# FPGA_Power.net
KiCad netlist of a schematic drawn in Altium Designer
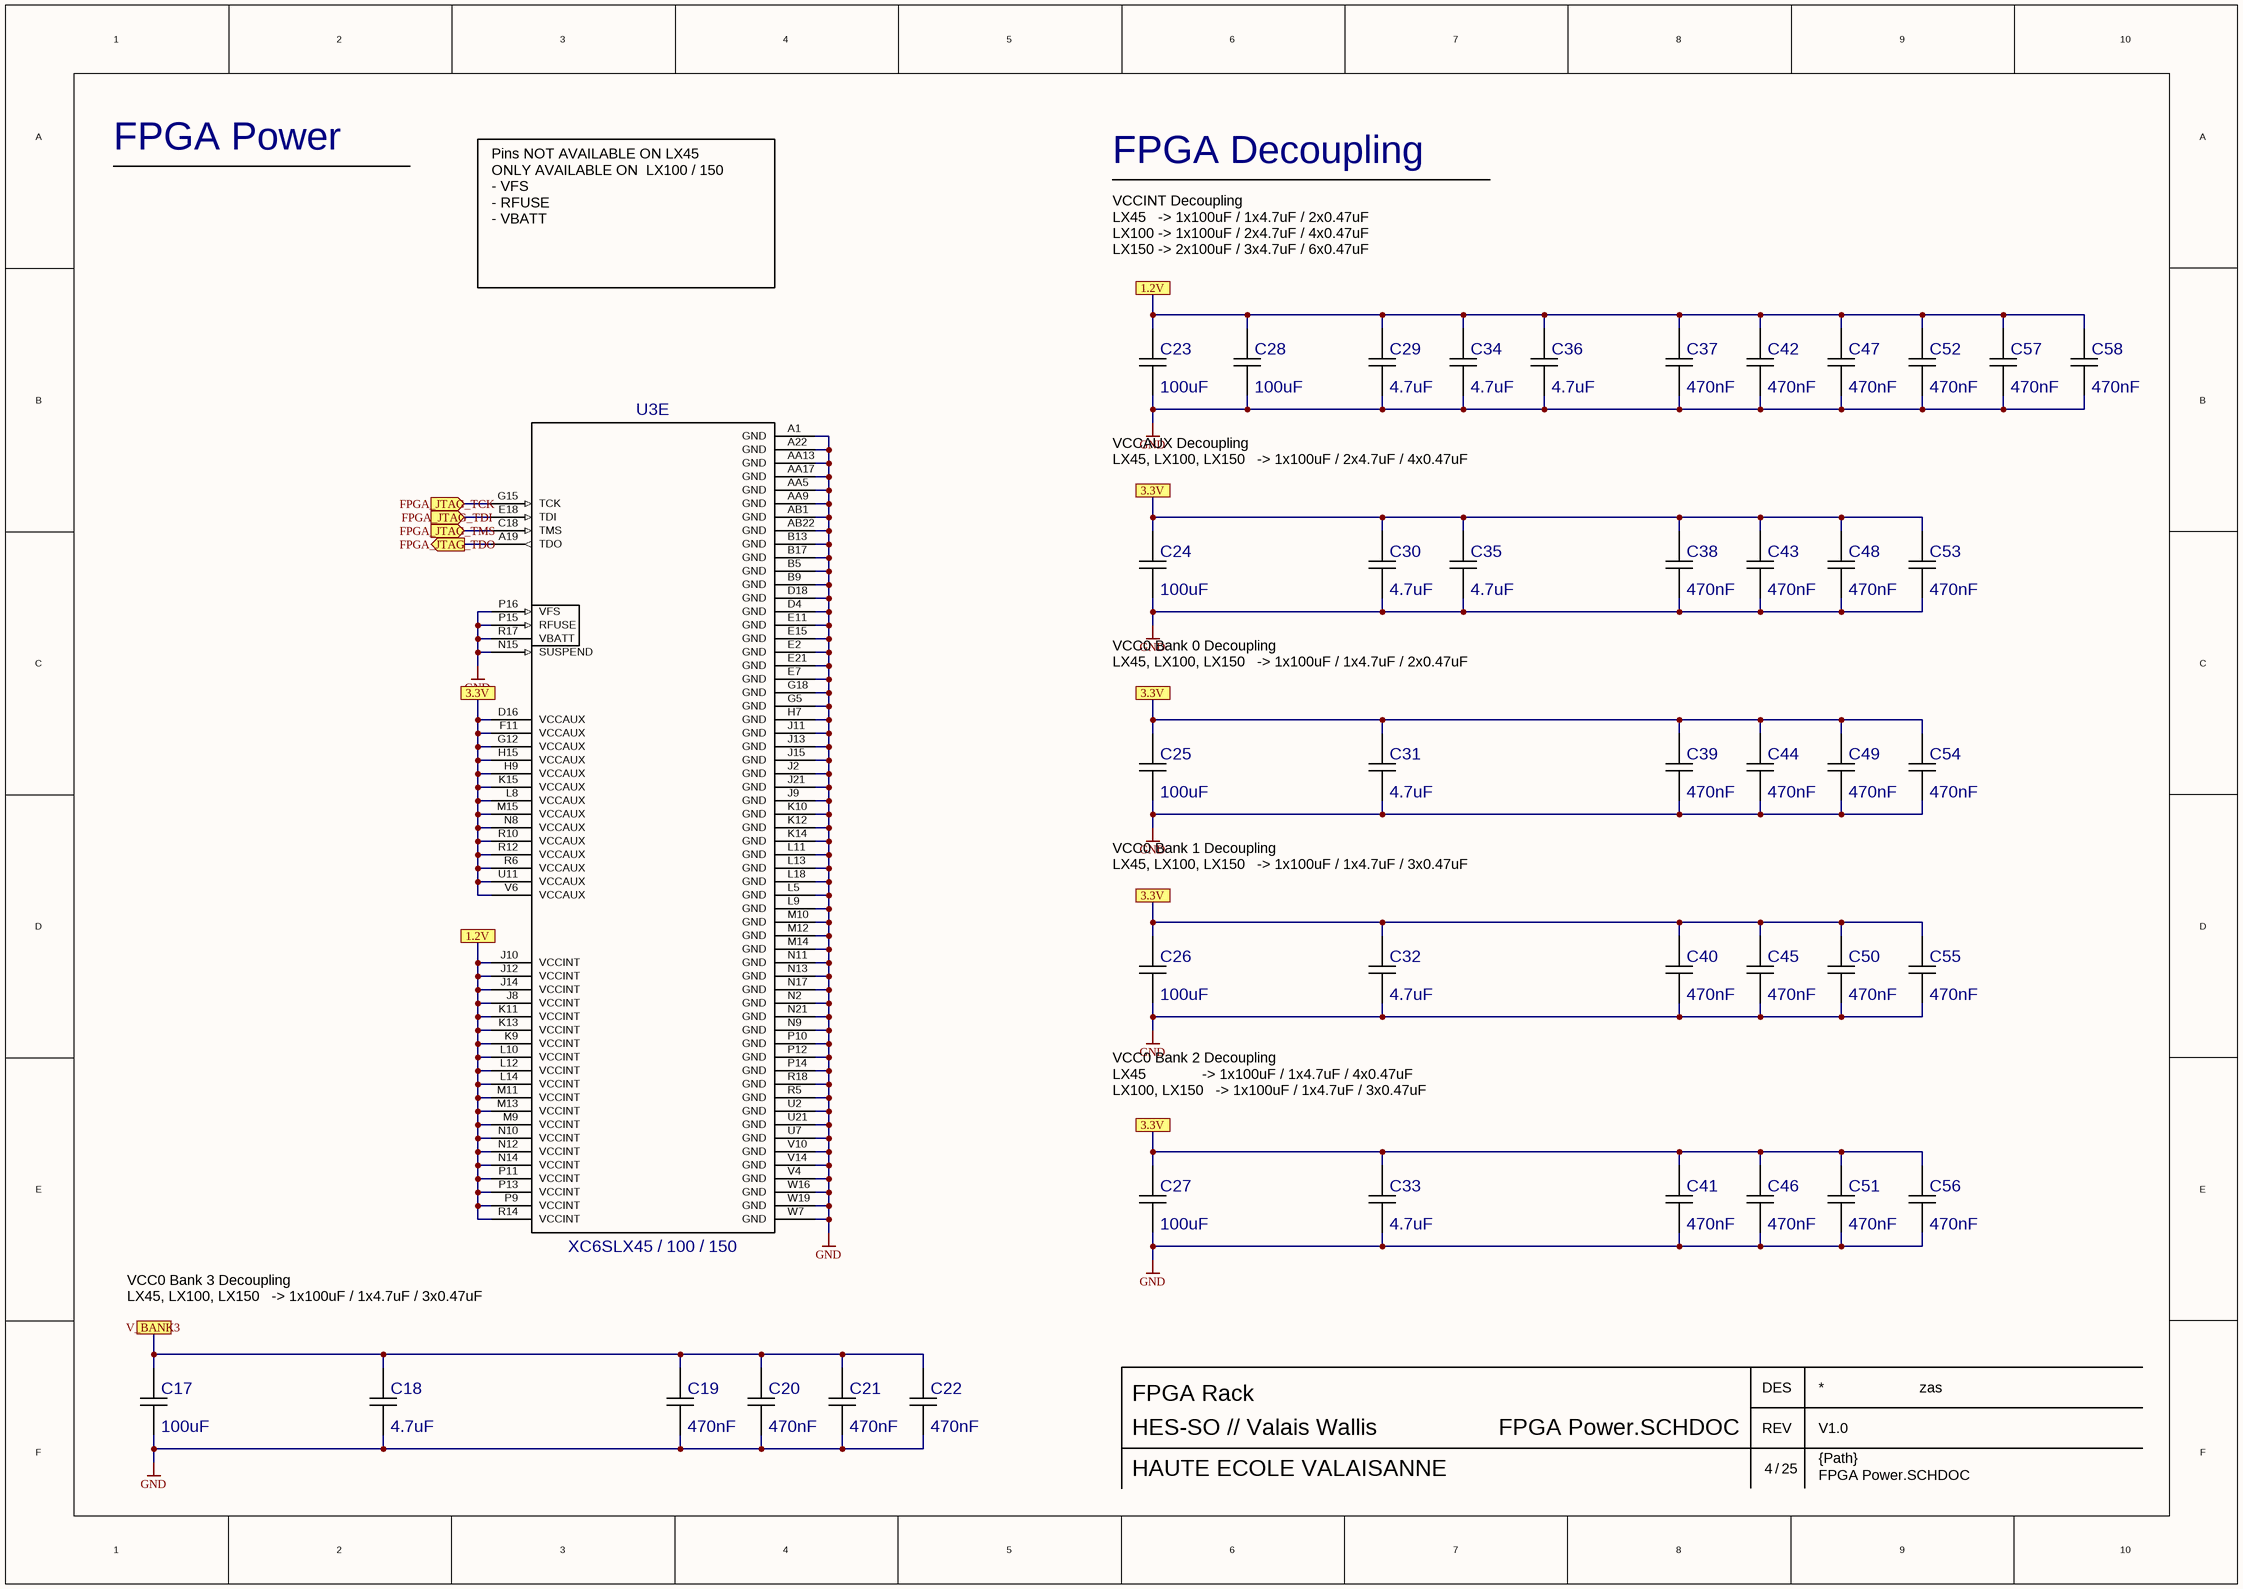
[diagram p0: FPGA Power.SCHDOC]

(export (version "E")
  (design (tool "Eeschema 10.0.6"))
  (components
    (comp (ref "C17")
      (value "100uF")
      (footprint "CC1206-MM")
      (description "Capacitor")
      (fields (field (name "Comment") "CAPS1206-MM"))
      (libsource (lib "*") (part "CAPS1206-MM"))
    )
    (comp (ref "C18")
      (value "4.7uF")
      (footprint "CC0805-MM")
      (description "Capacitor")
      (fields (field (name "Comment") "CAPS0805-MM"))
      (libsource (lib "*") (part "CAPS0805-MM"))
    )
    (comp (ref "C19")
      (value "470nF")
      (footprint "RC0603-MM")
      (description "Capacitor")
      (fields (field (name "Comment") "CAPS0603-MM"))
      (libsource (lib "*") (part "CAPS0603-MM"))
    )
    (comp (ref "C20")
      (value "470nF")
      (footprint "RC0603-MM")
      (description "Capacitor")
      (fields (field (name "Comment") "CAPS0603-MM"))
      (libsource (lib "*") (part "CAPS0603-MM"))
    )
    (comp (ref "C21")
      (value "470nF")
      (footprint "RC0603-MM")
      (description "Capacitor")
      (fields (field (name "Comment") "CAPS0603-MM"))
      (libsource (lib "*") (part "CAPS0603-MM"))
    )
    (comp (ref "C22")
      (value "470nF")
      (footprint "RC0603-MM")
      (description "Capacitor")
      (fields (field (name "Comment") "CAPS0603-MM"))
      (libsource (lib "*") (part "CAPS0603-MM"))
    )
    (comp (ref "C23")
      (value "100uF")
      (footprint "CC1206-MM")
      (description "Capacitor")
      (fields (field (name "Comment") "CAPS1206-MM"))
      (libsource (lib "*") (part "CAPS1206-MM"))
    )
    (comp (ref "C24")
      (value "100uF")
      (footprint "CC1206-MM")
      (description "Capacitor")
      (fields (field (name "Comment") "CAPS1206-MM"))
      (libsource (lib "*") (part "CAPS1206-MM"))
    )
    (comp (ref "C25")
      (value "100uF")
      (footprint "CC1206-MM")
      (description "Capacitor")
      (fields (field (name "Comment") "CAPS1206-MM"))
      (libsource (lib "*") (part "CAPS1206-MM"))
    )
    (comp (ref "C26")
      (value "100uF")
      (footprint "CC1206-MM")
      (description "Capacitor")
      (fields (field (name "Comment") "CAPS1206-MM"))
      (libsource (lib "*") (part "CAPS1206-MM"))
    )
    (comp (ref "C27")
      (value "100uF")
      (footprint "CC1206-MM")
      (description "Capacitor")
      (fields (field (name "Comment") "CAPS1206-MM"))
      (libsource (lib "*") (part "CAPS1206-MM"))
    )
    (comp (ref "C28")
      (value "100uF")
      (footprint "CC1206-MM")
      (description "Capacitor")
      (fields (field (name "Comment") "CAPS1206-MM"))
      (libsource (lib "*") (part "CAPS1206-MM"))
    )
    (comp (ref "C29")
      (value "4.7uF")
      (footprint "CC0805-MM")
      (description "Capacitor")
      (fields (field (name "Comment") "CAPS0805-MM"))
      (libsource (lib "*") (part "CAPS0805-MM"))
    )
    (comp (ref "C30")
      (value "4.7uF")
      (footprint "CC0805-MM")
      (description "Capacitor")
      (fields (field (name "Comment") "CAPS0805-MM"))
      (libsource (lib "*") (part "CAPS0805-MM"))
    )
    (comp (ref "C31")
      (value "4.7uF")
      (footprint "CC0805-MM")
      (description "Capacitor")
      (fields (field (name "Comment") "CAPS0805-MM"))
      (libsource (lib "*") (part "CAPS0805-MM"))
    )
    (comp (ref "C32")
      (value "4.7uF")
      (footprint "CC0805-MM")
      (description "Capacitor")
      (fields (field (name "Comment") "CAPS0805-MM"))
      (libsource (lib "*") (part "CAPS0805-MM"))
    )
    (comp (ref "C33")
      (value "4.7uF")
      (footprint "CC0805-MM")
      (description "Capacitor")
      (fields (field (name "Comment") "CAPS0805-MM"))
      (libsource (lib "*") (part "CAPS0805-MM"))
    )
    (comp (ref "C34")
      (value "4.7uF")
      (footprint "CC0805-MM")
      (description "Capacitor")
      (fields (field (name "Comment") "CAPS0805-MM"))
      (libsource (lib "*") (part "CAPS0805-MM"))
    )
    (comp (ref "C35")
      (value "4.7uF")
      (footprint "CC0805-MM")
      (description "Capacitor")
      (fields (field (name "Comment") "CAPS0805-MM"))
      (libsource (lib "*") (part "CAPS0805-MM"))
    )
    (comp (ref "C36")
      (value "4.7uF")
      (footprint "CC0805-MM")
      (description "Capacitor")
      (fields (field (name "Comment") "CAPS0805-MM"))
      (libsource (lib "*") (part "CAPS0805-MM"))
    )
    (comp (ref "C37")
      (value "470nF")
      (footprint "RC0603-MM")
      (description "Capacitor")
      (fields (field (name "Comment") "CAPS0603-MM"))
      (libsource (lib "*") (part "CAPS0603-MM"))
    )
    (comp (ref "C38")
      (value "470nF")
      (footprint "RC0603-MM")
      (description "Capacitor")
      (fields (field (name "Comment") "CAPS0603-MM"))
      (libsource (lib "*") (part "CAPS0603-MM"))
    )
    (comp (ref "C39")
      (value "470nF")
      (footprint "RC0603-MM")
      (description "Capacitor")
      (fields (field (name "Comment") "CAPS0603-MM"))
      (libsource (lib "*") (part "CAPS0603-MM"))
    )
    (comp (ref "C40")
      (value "470nF")
      (footprint "RC0603-MM")
      (description "Capacitor")
      (fields (field (name "Comment") "CAPS0603-MM"))
      (libsource (lib "*") (part "CAPS0603-MM"))
    )
    (comp (ref "C41")
      (value "470nF")
      (footprint "RC0603-MM")
      (description "Capacitor")
      (fields (field (name "Comment") "CAPS0603-MM"))
      (libsource (lib "*") (part "CAPS0603-MM"))
    )
    (comp (ref "C42")
      (value "470nF")
      (footprint "RC0603-MM")
      (description "Capacitor")
      (fields (field (name "Comment") "CAPS0603-MM"))
      (libsource (lib "*") (part "CAPS0603-MM"))
    )
    (comp (ref "C43")
      (value "470nF")
      (footprint "RC0603-MM")
      (description "Capacitor")
      (fields (field (name "Comment") "CAPS0603-MM"))
      (libsource (lib "*") (part "CAPS0603-MM"))
    )
    (comp (ref "C44")
      (value "470nF")
      (footprint "RC0603-MM")
      (description "Capacitor")
      (fields (field (name "Comment") "CAPS0603-MM"))
      (libsource (lib "*") (part "CAPS0603-MM"))
    )
    (comp (ref "C45")
      (value "470nF")
      (footprint "RC0603-MM")
      (description "Capacitor")
      (fields (field (name "Comment") "CAPS0603-MM"))
      (libsource (lib "*") (part "CAPS0603-MM"))
    )
    (comp (ref "C46")
      (value "470nF")
      (footprint "RC0603-MM")
      (description "Capacitor")
      (fields (field (name "Comment") "CAPS0603-MM"))
      (libsource (lib "*") (part "CAPS0603-MM"))
    )
    (comp (ref "C47")
      (value "470nF")
      (footprint "RC0603-MM")
      (description "Capacitor")
      (fields (field (name "Comment") "CAPS0603-MM"))
      (libsource (lib "*") (part "CAPS0603-MM"))
    )
    (comp (ref "C48")
      (value "470nF")
      (footprint "RC0603-MM")
      (description "Capacitor")
      (fields (field (name "Comment") "CAPS0603-MM"))
      (libsource (lib "*") (part "CAPS0603-MM"))
    )
    (comp (ref "C49")
      (value "470nF")
      (footprint "RC0603-MM")
      (description "Capacitor")
      (fields (field (name "Comment") "CAPS0603-MM"))
      (libsource (lib "*") (part "CAPS0603-MM"))
    )
    (comp (ref "C50")
      (value "470nF")
      (footprint "RC0603-MM")
      (description "Capacitor")
      (fields (field (name "Comment") "CAPS0603-MM"))
      (libsource (lib "*") (part "CAPS0603-MM"))
    )
    (comp (ref "C51")
      (value "470nF")
      (footprint "RC0603-MM")
      (description "Capacitor")
      (fields (field (name "Comment") "CAPS0603-MM"))
      (libsource (lib "*") (part "CAPS0603-MM"))
    )
    (comp (ref "C52")
      (value "470nF")
      (footprint "RC0603-MM")
      (description "Capacitor")
      (fields (field (name "Comment") "CAPS0603-MM"))
      (libsource (lib "*") (part "CAPS0603-MM"))
    )
    (comp (ref "C53")
      (value "470nF")
      (footprint "RC0603-MM")
      (description "Capacitor")
      (fields (field (name "Comment") "CAPS0603-MM"))
      (libsource (lib "*") (part "CAPS0603-MM"))
    )
    (comp (ref "C54")
      (value "470nF")
      (footprint "RC0603-MM")
      (description "Capacitor")
      (fields (field (name "Comment") "CAPS0603-MM"))
      (libsource (lib "*") (part "CAPS0603-MM"))
    )
    (comp (ref "C55")
      (value "470nF")
      (footprint "RC0603-MM")
      (description "Capacitor")
      (fields (field (name "Comment") "CAPS0603-MM"))
      (libsource (lib "*") (part "CAPS0603-MM"))
    )
    (comp (ref "C56")
      (value "470nF")
      (footprint "RC0603-MM")
      (description "Capacitor")
      (fields (field (name "Comment") "CAPS0603-MM"))
      (libsource (lib "*") (part "CAPS0603-MM"))
    )
    (comp (ref "C57")
      (value "470nF")
      (footprint "RC0603-MM")
      (description "Capacitor")
      (fields (field (name "Comment") "CAPS0603-MM"))
      (libsource (lib "*") (part "CAPS0603-MM"))
    )
    (comp (ref "C58")
      (value "470nF")
      (footprint "RC0603-MM")
      (description "Capacitor")
      (fields (field (name "Comment") "CAPS0603-MM"))
      (libsource (lib "*") (part "CAPS0603-MM"))
    )
    (comp (ref "U3")
      (value "XC6SLX45 / 100 / 150")
      (footprint "BGA23X23-FG484")
      (description "XC6SLX150 FGG484")
      (libsource (lib "*") (part "XC6SLX150 FGG484"))
    )
  )
  (nets
    (net (code "3") (name "/FPGA_JTAG_TCK") (class "Default")
      (node (ref "U3") (pin "G15") (pinfunction "TCK_G15") (pintype "input"))
    )
    (net (code "4") (name "/FPGA_JTAG_TDI") (class "Default")
      (node (ref "U3") (pin "E18") (pinfunction "TDI_E18") (pintype "input"))
    )
    (net (code "5") (name "/FPGA_JTAG_TDO") (class "Default")
      (node (ref "U3") (pin "A19") (pinfunction "TDO_A19") (pintype "output"))
    )
    (net (code "6") (name "/FPGA_JTAG_TMS") (class "Default")
      (node (ref "U3") (pin "C18") (pinfunction "TMS_C18") (pintype "input"))
    )
    (net (code "8") (name "GND") (class "Default")
      (node (ref "C17") (pin "1") (pinfunction "1_1") (pintype "passive"))
      (node (ref "C18") (pin "1") (pinfunction "1_1") (pintype "passive"))
      (node (ref "C19") (pin "1") (pinfunction "1_1") (pintype "passive"))
      (node (ref "C20") (pin "1") (pinfunction "1_1") (pintype "passive"))
      (node (ref "C21") (pin "1") (pinfunction "1_1") (pintype "passive"))
      (node (ref "C22") (pin "1") (pinfunction "1_1") (pintype "passive"))
      (node (ref "C23") (pin "1") (pinfunction "1_1") (pintype "passive"))
      (node (ref "C24") (pin "1") (pinfunction "1_1") (pintype "passive"))
      (node (ref "C25") (pin "1") (pinfunction "1_1") (pintype "passive"))
      (node (ref "C26") (pin "1") (pinfunction "1_1") (pintype "passive"))
      (node (ref "C27") (pin "1") (pinfunction "1_1") (pintype "passive"))
      (node (ref "C28") (pin "1") (pinfunction "1_1") (pintype "passive"))
      (node (ref "C29") (pin "1") (pinfunction "1_1") (pintype "passive"))
      (node (ref "C30") (pin "1") (pinfunction "1_1") (pintype "passive"))
      (node (ref "C31") (pin "1") (pinfunction "1_1") (pintype "passive"))
      (node (ref "C32") (pin "1") (pinfunction "1_1") (pintype "passive"))
      (node (ref "C33") (pin "1") (pinfunction "1_1") (pintype "passive"))
      (node (ref "C34") (pin "1") (pinfunction "1_1") (pintype "passive"))
      (node (ref "C35") (pin "1") (pinfunction "1_1") (pintype "passive"))
      (node (ref "C36") (pin "1") (pinfunction "1_1") (pintype "passive"))
      (node (ref "C37") (pin "1") (pinfunction "1_1") (pintype "passive"))
      (node (ref "C38") (pin "1") (pinfunction "1_1") (pintype "passive"))
      (node (ref "C39") (pin "1") (pinfunction "1_1") (pintype "passive"))
      (node (ref "C40") (pin "1") (pinfunction "1_1") (pintype "passive"))
      (node (ref "C41") (pin "1") (pinfunction "1_1") (pintype "passive"))
      (node (ref "C42") (pin "1") (pinfunction "1_1") (pintype "passive"))
      (node (ref "C43") (pin "1") (pinfunction "1_1") (pintype "passive"))
      (node (ref "C44") (pin "1") (pinfunction "1_1") (pintype "passive"))
      (node (ref "C45") (pin "1") (pinfunction "1_1") (pintype "passive"))
      (node (ref "C46") (pin "1") (pinfunction "1_1") (pintype "passive"))
      (node (ref "C47") (pin "1") (pinfunction "1_1") (pintype "passive"))
      (node (ref "C48") (pin "1") (pinfunction "1_1") (pintype "passive"))
      (node (ref "C49") (pin "1") (pinfunction "1_1") (pintype "passive"))
      (node (ref "C50") (pin "1") (pinfunction "1_1") (pintype "passive"))
      (node (ref "C51") (pin "1") (pinfunction "1_1") (pintype "passive"))
      (node (ref "C52") (pin "1") (pinfunction "1_1") (pintype "passive"))
      (node (ref "C53") (pin "1") (pinfunction "1_1") (pintype "passive"))
      (node (ref "C54") (pin "1") (pinfunction "1_1") (pintype "passive"))
      (node (ref "C55") (pin "1") (pinfunction "1_1") (pintype "passive"))
      (node (ref "C56") (pin "1") (pinfunction "1_1") (pintype "passive"))
      (node (ref "C57") (pin "1") (pinfunction "1_1") (pintype "passive"))
      (node (ref "C58") (pin "1") (pinfunction "1_1") (pintype "passive"))
      (node (ref "U3") (pin "A1") (pinfunction "GND_A1") (pintype "power_in"))
      (node (ref "U3") (pin "A22") (pinfunction "GND_A22") (pintype "power_in"))
      (node (ref "U3") (pin "AA13") (pinfunction "GND_AA13") (pintype "power_in"))
      (node (ref "U3") (pin "AA17") (pinfunction "GND_AA17") (pintype "power_in"))
      (node (ref "U3") (pin "AA5") (pinfunction "GND_AA5") (pintype "power_in"))
      (node (ref "U3") (pin "AA9") (pinfunction "GND_AA9") (pintype "power_in"))
      (node (ref "U3") (pin "AB1") (pinfunction "GND_AB1") (pintype "power_in"))
      (node (ref "U3") (pin "AB22") (pinfunction "GND_AB22") (pintype "power_in"))
      (node (ref "U3") (pin "B13") (pinfunction "GND_B13") (pintype "power_in"))
      (node (ref "U3") (pin "B17") (pinfunction "GND_B17") (pintype "power_in"))
      (node (ref "U3") (pin "B5") (pinfunction "GND_B5") (pintype "power_in"))
      (node (ref "U3") (pin "B9") (pinfunction "GND_B9") (pintype "power_in"))
      (node (ref "U3") (pin "D18") (pinfunction "GND_D18") (pintype "power_in"))
      (node (ref "U3") (pin "D4") (pinfunction "GND_D4") (pintype "power_in"))
      (node (ref "U3") (pin "E11") (pinfunction "GND_E11") (pintype "power_in"))
      (node (ref "U3") (pin "E15") (pinfunction "GND_E15") (pintype "power_in"))
      (node (ref "U3") (pin "E2") (pinfunction "GND_E2") (pintype "power_in"))
      (node (ref "U3") (pin "E21") (pinfunction "GND_E21") (pintype "power_in"))
      (node (ref "U3") (pin "E7") (pinfunction "GND_E7") (pintype "power_in"))
      (node (ref "U3") (pin "G18") (pinfunction "GND_G18") (pintype "power_in"))
      (node (ref "U3") (pin "G5") (pinfunction "GND_G5") (pintype "power_in"))
      (node (ref "U3") (pin "H7") (pinfunction "GND_H7") (pintype "power_in"))
      (node (ref "U3") (pin "J11") (pinfunction "GND_J11") (pintype "power_in"))
      (node (ref "U3") (pin "J13") (pinfunction "GND_J13") (pintype "power_in"))
      (node (ref "U3") (pin "J15") (pinfunction "GND_J15") (pintype "power_in"))
      (node (ref "U3") (pin "J2") (pinfunction "GND_J2") (pintype "power_in"))
      (node (ref "U3") (pin "J21") (pinfunction "GND_J21") (pintype "power_in"))
      (node (ref "U3") (pin "J9") (pinfunction "GND_J9") (pintype "power_in"))
      (node (ref "U3") (pin "K10") (pinfunction "GND_K10") (pintype "power_in"))
      (node (ref "U3") (pin "K12") (pinfunction "GND_K12") (pintype "power_in"))
      (node (ref "U3") (pin "K14") (pinfunction "GND_K14") (pintype "power_in"))
      (node (ref "U3") (pin "L11") (pinfunction "GND_L11") (pintype "power_in"))
      (node (ref "U3") (pin "L13") (pinfunction "GND_L13") (pintype "power_in"))
      (node (ref "U3") (pin "L18") (pinfunction "GND_L18") (pintype "power_in"))
      (node (ref "U3") (pin "L5") (pinfunction "GND_L5") (pintype "power_in"))
      (node (ref "U3") (pin "L9") (pinfunction "GND_L9") (pintype "power_in"))
      (node (ref "U3") (pin "M10") (pinfunction "GND_M10") (pintype "power_in"))
      (node (ref "U3") (pin "M12") (pinfunction "GND_M12") (pintype "power_in"))
      (node (ref "U3") (pin "M14") (pinfunction "GND_M14") (pintype "power_in"))
      (node (ref "U3") (pin "N11") (pinfunction "GND_N11") (pintype "power_in"))
      (node (ref "U3") (pin "N13") (pinfunction "GND_N13") (pintype "power_in"))
      (node (ref "U3") (pin "N15") (pinfunction "SUSPEND_N15") (pintype "input"))
      (node (ref "U3") (pin "N17") (pinfunction "GND_N17") (pintype "power_in"))
      (node (ref "U3") (pin "N2") (pinfunction "GND_N2") (pintype "power_in"))
      (node (ref "U3") (pin "N21") (pinfunction "GND_N21") (pintype "power_in"))
      (node (ref "U3") (pin "N9") (pinfunction "GND_N9") (pintype "power_in"))
      (node (ref "U3") (pin "P10") (pinfunction "GND_P10") (pintype "power_in"))
      (node (ref "U3") (pin "P12") (pinfunction "GND_P12") (pintype "power_in"))
      (node (ref "U3") (pin "P14") (pinfunction "GND_P14") (pintype "power_in"))
      (node (ref "U3") (pin "P15") (pinfunction "RFUSE_P15") (pintype "input"))
      (node (ref "U3") (pin "P16") (pinfunction "VFS_P16") (pintype "input"))
      (node (ref "U3") (pin "R17") (pinfunction "VBATT_R17") (pintype "power_in"))
      (node (ref "U3") (pin "R18") (pinfunction "GND_R18") (pintype "power_in"))
      (node (ref "U3") (pin "R5") (pinfunction "GND_R5") (pintype "power_in"))
      (node (ref "U3") (pin "U2") (pinfunction "GND_U2") (pintype "power_in"))
      (node (ref "U3") (pin "U21") (pinfunction "GND_U21") (pintype "power_in"))
      (node (ref "U3") (pin "U7") (pinfunction "GND_U7") (pintype "power_in"))
      (node (ref "U3") (pin "V10") (pinfunction "GND_V10") (pintype "power_in"))
      (node (ref "U3") (pin "V14") (pinfunction "GND_V14") (pintype "power_in"))
      (node (ref "U3") (pin "V4") (pinfunction "GND_V4") (pintype "power_in"))
      (node (ref "U3") (pin "W16") (pinfunction "GND_W16") (pintype "power_in"))
      (node (ref "U3") (pin "W19") (pinfunction "GND_W19") (pintype "power_in"))
      (node (ref "U3") (pin "W7") (pinfunction "GND_W7") (pintype "power_in"))
    )
    (net (code "9") (name "Net-(C17-Pad2)") (class "Default")
      (node (ref "C17") (pin "2") (pinfunction "2_2") (pintype "passive"))
      (node (ref "C18") (pin "2") (pinfunction "2_2") (pintype "passive"))
      (node (ref "C19") (pin "2") (pinfunction "2_2") (pintype "passive"))
      (node (ref "C20") (pin "2") (pinfunction "2_2") (pintype "passive"))
      (node (ref "C21") (pin "2") (pinfunction "2_2") (pintype "passive"))
      (node (ref "C22") (pin "2") (pinfunction "2_2") (pintype "passive"))
    )
    (net (code "10") (name "Net-(C23-Pad2)") (class "Default")
      (node (ref "C23") (pin "2") (pinfunction "2_2") (pintype "passive"))
      (node (ref "C28") (pin "2") (pinfunction "2_2") (pintype "passive"))
      (node (ref "C29") (pin "2") (pinfunction "2_2") (pintype "passive"))
      (node (ref "C34") (pin "2") (pinfunction "2_2") (pintype "passive"))
      (node (ref "C36") (pin "2") (pinfunction "2_2") (pintype "passive"))
      (node (ref "C37") (pin "2") (pinfunction "2_2") (pintype "passive"))
      (node (ref "C42") (pin "2") (pinfunction "2_2") (pintype "passive"))
      (node (ref "C47") (pin "2") (pinfunction "2_2") (pintype "passive"))
      (node (ref "C52") (pin "2") (pinfunction "2_2") (pintype "passive"))
      (node (ref "C57") (pin "2") (pinfunction "2_2") (pintype "passive"))
      (node (ref "C58") (pin "2") (pinfunction "2_2") (pintype "passive"))
    )
    (net (code "11") (name "Net-(C24-Pad2)") (class "Default")
      (node (ref "C24") (pin "2") (pinfunction "2_2") (pintype "passive"))
      (node (ref "C30") (pin "2") (pinfunction "2_2") (pintype "passive"))
      (node (ref "C35") (pin "2") (pinfunction "2_2") (pintype "passive"))
      (node (ref "C38") (pin "2") (pinfunction "2_2") (pintype "passive"))
      (node (ref "C43") (pin "2") (pinfunction "2_2") (pintype "passive"))
      (node (ref "C48") (pin "2") (pinfunction "2_2") (pintype "passive"))
      (node (ref "C53") (pin "2") (pinfunction "2_2") (pintype "passive"))
    )
    (net (code "12") (name "Net-(C25-Pad2)") (class "Default")
      (node (ref "C25") (pin "2") (pinfunction "2_2") (pintype "passive"))
      (node (ref "C31") (pin "2") (pinfunction "2_2") (pintype "passive"))
      (node (ref "C39") (pin "2") (pinfunction "2_2") (pintype "passive"))
      (node (ref "C44") (pin "2") (pinfunction "2_2") (pintype "passive"))
      (node (ref "C49") (pin "2") (pinfunction "2_2") (pintype "passive"))
      (node (ref "C54") (pin "2") (pinfunction "2_2") (pintype "passive"))
    )
    (net (code "13") (name "Net-(C26-Pad2)") (class "Default")
      (node (ref "C26") (pin "2") (pinfunction "2_2") (pintype "passive"))
      (node (ref "C32") (pin "2") (pinfunction "2_2") (pintype "passive"))
      (node (ref "C40") (pin "2") (pinfunction "2_2") (pintype "passive"))
      (node (ref "C45") (pin "2") (pinfunction "2_2") (pintype "passive"))
      (node (ref "C50") (pin "2") (pinfunction "2_2") (pintype "passive"))
      (node (ref "C55") (pin "2") (pinfunction "2_2") (pintype "passive"))
    )
    (net (code "14") (name "Net-(C27-Pad2)") (class "Default")
      (node (ref "C27") (pin "2") (pinfunction "2_2") (pintype "passive"))
      (node (ref "C33") (pin "2") (pinfunction "2_2") (pintype "passive"))
      (node (ref "C41") (pin "2") (pinfunction "2_2") (pintype "passive"))
      (node (ref "C46") (pin "2") (pinfunction "2_2") (pintype "passive"))
      (node (ref "C51") (pin "2") (pinfunction "2_2") (pintype "passive"))
      (node (ref "C56") (pin "2") (pinfunction "2_2") (pintype "passive"))
    )
    (net (code "15") (name "Net-(U3E-VCCAUX-PadD16)") (class "Default")
      (node (ref "U3") (pin "D16") (pinfunction "VCCAUX_D16") (pintype "power_in"))
      (node (ref "U3") (pin "F11") (pinfunction "VCCAUX_F11") (pintype "power_in"))
      (node (ref "U3") (pin "G12") (pinfunction "VCCAUX_G12") (pintype "power_in"))
      (node (ref "U3") (pin "H15") (pinfunction "VCCAUX_H15") (pintype "power_in"))
      (node (ref "U3") (pin "H9") (pinfunction "VCCAUX_H9") (pintype "power_in"))
      (node (ref "U3") (pin "K15") (pinfunction "VCCAUX_K15") (pintype "power_in"))
      (node (ref "U3") (pin "L8") (pinfunction "VCCAUX_L8") (pintype "power_in"))
      (node (ref "U3") (pin "M15") (pinfunction "VCCAUX_M15") (pintype "power_in"))
      (node (ref "U3") (pin "N8") (pinfunction "VCCAUX_N8") (pintype "power_in"))
      (node (ref "U3") (pin "R10") (pinfunction "VCCAUX_R10") (pintype "power_in"))
      (node (ref "U3") (pin "R12") (pinfunction "VCCAUX_R12") (pintype "power_in"))
      (node (ref "U3") (pin "R6") (pinfunction "VCCAUX_R6") (pintype "power_in"))
      (node (ref "U3") (pin "U11") (pinfunction "VCCAUX_U11") (pintype "power_in"))
      (node (ref "U3") (pin "V6") (pinfunction "VCCAUX_V6") (pintype "power_in"))
    )
    (net (code "16") (name "Net-(U3E-VCCINT-PadJ10)") (class "Default")
      (node (ref "U3") (pin "J10") (pinfunction "VCCINT_J10") (pintype "power_in"))
      (node (ref "U3") (pin "J12") (pinfunction "VCCINT_J12") (pintype "power_in"))
      (node (ref "U3") (pin "J14") (pinfunction "VCCINT_J14") (pintype "power_in"))
      (node (ref "U3") (pin "J8") (pinfunction "VCCINT_J8") (pintype "power_in"))
      (node (ref "U3") (pin "K11") (pinfunction "VCCINT_K11") (pintype "power_in"))
      (node (ref "U3") (pin "K13") (pinfunction "VCCINT_K13") (pintype "power_in"))
      (node (ref "U3") (pin "K9") (pinfunction "VCCINT_K9") (pintype "power_in"))
      (node (ref "U3") (pin "L10") (pinfunction "VCCINT_L10") (pintype "power_in"))
      (node (ref "U3") (pin "L12") (pinfunction "VCCINT_L12") (pintype "power_in"))
      (node (ref "U3") (pin "L14") (pinfunction "VCCINT_L14") (pintype "power_in"))
      (node (ref "U3") (pin "M11") (pinfunction "VCCINT_M11") (pintype "power_in"))
      (node (ref "U3") (pin "M13") (pinfunction "VCCINT_M13") (pintype "power_in"))
      (node (ref "U3") (pin "M9") (pinfunction "VCCINT_M9") (pintype "power_in"))
      (node (ref "U3") (pin "N10") (pinfunction "VCCINT_N10") (pintype "power_in"))
      (node (ref "U3") (pin "N12") (pinfunction "VCCINT_N12") (pintype "power_in"))
      (node (ref "U3") (pin "N14") (pinfunction "VCCINT_N14") (pintype "power_in"))
      (node (ref "U3") (pin "P11") (pinfunction "VCCINT_P11") (pintype "power_in"))
      (node (ref "U3") (pin "P13") (pinfunction "VCCINT_P13") (pintype "power_in"))
      (node (ref "U3") (pin "P9") (pinfunction "VCCINT_P9") (pintype "power_in"))
      (node (ref "U3") (pin "R14") (pinfunction "VCCINT_R14") (pintype "power_in"))
    )
  )
)
